# SCH_gps-tracker_2023-06-04.net
KiCad netlist of a schematic drawn in EasyEDA
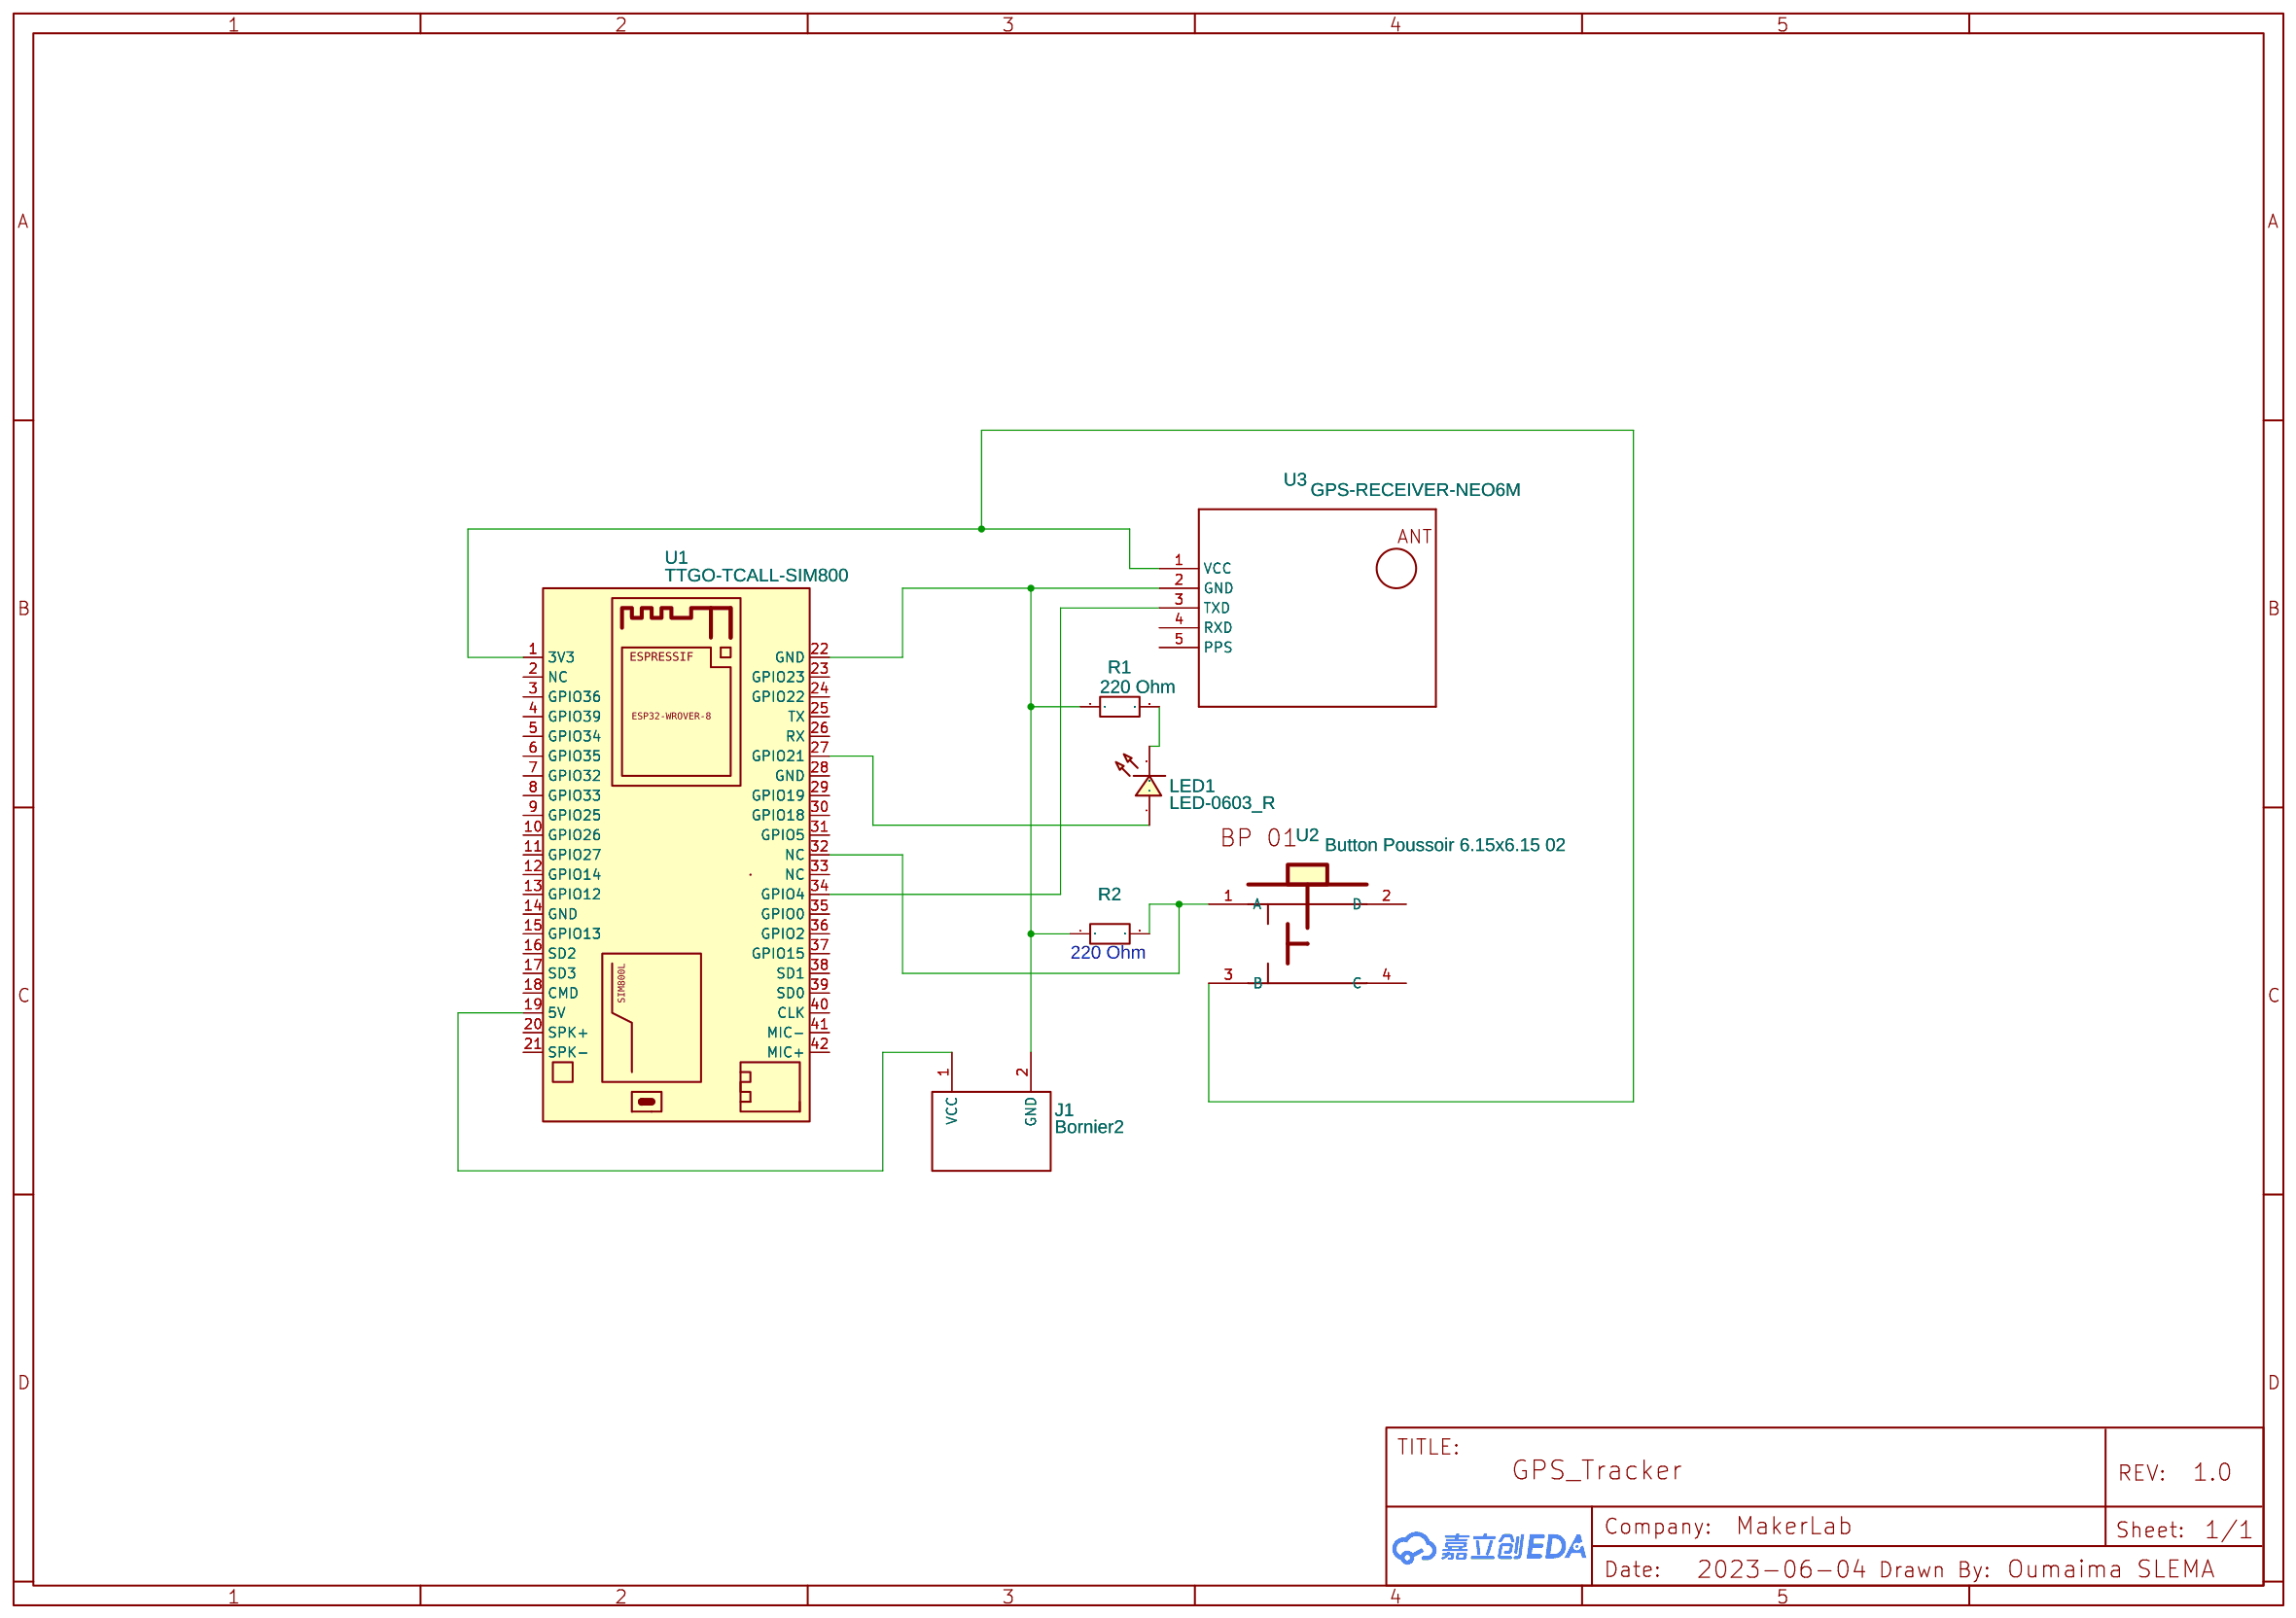
[diagram p0: schematic sheet]

(export (version "E")
  (design (tool "Eeschema 10.0.6"))
  (components
    (comp (ref "J1") (value "Bornier2") (libsource (lib "") (part "Bornier2")))
    (comp (ref "LED1")
      (value "LED-0603_R")
      (fields
        (field (name "BOM_Manufacturer Part") "19-217/R6C-AL1M2VY/3T")
        (field (name "BOM_Supplier Part") "C72044")
      )
      (libsource (lib "") (part "LED-0603_R"))
    )
    (comp (ref "R1") (value "220 Ohm") (libsource (lib "") (part "R_0603_EU")))
    (comp (ref "R2") (value "1k") (libsource (lib "") (part "R_0603_EU")))
    (comp (ref "U1") (value "TTGO-TCALL-SIM800") (libsource (lib "") (part "TTGO-TCALL-SIM800")))
    (comp (ref "U2")
      (value "Button Poussoir 6.15x6.15 02")
      (libsource (lib "") (part "Button Poussoir 6.15x6.15 02"))
    )
    (comp (ref "U3") (value "GPS-RECEIVER-NEO6M") (libsource (lib "") (part "GPS-RECEIVER-NEO6M")))
  )
  (nets
    (net (code "1") (name "Net-(J1-GND)") (class "Default")
      (node (ref "J1") (pin "2") (pinfunction "GND_2") (pintype "unspecified"))
      (node (ref "R1") (pin "1") (pinfunction "1_1") (pintype "unspecified"))
      (node (ref "R2") (pin "1") (pinfunction "1_1") (pintype "unspecified"))
      (node (ref "U1") (pin "22") (pinfunction "GND_22") (pintype "bidirectional"))
      (node (ref "U3") (pin "2") (pinfunction "GND_2") (pintype "unspecified"))
    )
    (net (code "2") (name "Net-(J1-VCC)") (class "Default")
      (node (ref "J1") (pin "1") (pinfunction "VCC_1") (pintype "unspecified"))
      (node (ref "U1") (pin "19") (pinfunction "5V_19") (pintype "bidirectional"))
    )
    (net (code "3") (name "Net-(LED1-Pad2)") (class "Default")
      (node (ref "LED1") (pin "2") (pinfunction "2_2") (pintype "unspecified"))
      (node (ref "R1") (pin "2") (pinfunction "2_2") (pintype "unspecified"))
    )
    (net (code "4") (name "Net-(U1-3V3)") (class "Default")
      (node (ref "U1") (pin "1") (pinfunction "3V3_1") (pintype "bidirectional"))
      (node (ref "U2") (pin "3") (pinfunction "B_3") (pintype "unspecified"))
      (node (ref "U3") (pin "1") (pinfunction "VCC_1") (pintype "unspecified"))
    )
    (net (code "5") (name "Net-(U1-GPIO4)") (class "Default")
      (node (ref "U1") (pin "34") (pinfunction "GPIO4_34") (pintype "unspecified"))
      (node (ref "U3") (pin "3") (pinfunction "TXD_3") (pintype "unspecified"))
    )
    (net (code "6") (name "Net-(U1-GPIO21)") (class "Default")
      (node (ref "LED1") (pin "1") (pinfunction "1_1") (pintype "unspecified"))
      (node (ref "U1") (pin "27") (pinfunction "GPIO21_27") (pintype "unspecified"))
    )
    (net (code "7") (name "Net-(U2-A)") (class "Default")
      (node (ref "R2") (pin "2") (pinfunction "2_2") (pintype "unspecified"))
      (node (ref "U1") (pin "32") (pinfunction "NC_32") (pintype "bidirectional"))
      (node (ref "U2") (pin "1") (pinfunction "A_1") (pintype "unspecified"))
    )
    (net (code "8") (name "unconnected-(U1-CLK-Pad40)") (class "Default")
      (node (ref "U1") (pin "40") (pinfunction "CLK_40") (pintype "unspecified"))
    )
    (net (code "9") (name "unconnected-(U1-CMD-Pad18)") (class "Default")
      (node (ref "U1") (pin "18") (pinfunction "CMD_18") (pintype "unspecified"))
    )
    (net (code "10") (name "unconnected-(U1-GND-Pad14)") (class "Default")
      (node (ref "U1") (pin "14") (pinfunction "GND_14") (pintype "bidirectional"))
    )
    (net (code "11") (name "unconnected-(U1-GND-Pad28)") (class "Default")
      (node (ref "U1") (pin "28") (pinfunction "GND_28") (pintype "bidirectional"))
    )
    (net (code "12") (name "unconnected-(U1-GPIO0-Pad35)") (class "Default")
      (node (ref "U1") (pin "35") (pinfunction "GPIO0_35") (pintype "unspecified"))
    )
    (net (code "13") (name "unconnected-(U1-GPIO2-Pad36)") (class "Default")
      (node (ref "U1") (pin "36") (pinfunction "GPIO2_36") (pintype "unspecified"))
    )
    (net (code "14") (name "unconnected-(U1-GPIO5-Pad31)") (class "Default")
      (node (ref "U1") (pin "31") (pinfunction "GPIO5_31") (pintype "unspecified"))
    )
    (net (code "15") (name "unconnected-(U1-GPIO12-Pad13)") (class "Default")
      (node (ref "U1") (pin "13") (pinfunction "GPIO12_13") (pintype "unspecified"))
    )
    (net (code "16") (name "unconnected-(U1-GPIO13-Pad15)") (class "Default")
      (node (ref "U1") (pin "15") (pinfunction "GPIO13_15") (pintype "unspecified"))
    )
    (net (code "17") (name "unconnected-(U1-GPIO14-Pad12)") (class "Default")
      (node (ref "U1") (pin "12") (pinfunction "GPIO14_12") (pintype "unspecified"))
    )
    (net (code "18") (name "unconnected-(U1-GPIO15-Pad37)") (class "Default")
      (node (ref "U1") (pin "37") (pinfunction "GPIO15_37") (pintype "unspecified"))
    )
    (net (code "19") (name "unconnected-(U1-GPIO18-Pad30)") (class "Default")
      (node (ref "U1") (pin "30") (pinfunction "GPIO18_30") (pintype "unspecified"))
    )
    (net (code "20") (name "unconnected-(U1-GPIO19-Pad29)") (class "Default")
      (node (ref "U1") (pin "29") (pinfunction "GPIO19_29") (pintype "unspecified"))
    )
    (net (code "21") (name "unconnected-(U1-GPIO22-Pad24)") (class "Default")
      (node (ref "U1") (pin "24") (pinfunction "GPIO22_24") (pintype "unspecified"))
    )
    (net (code "22") (name "unconnected-(U1-GPIO23-Pad23)") (class "Default")
      (node (ref "U1") (pin "23") (pinfunction "GPIO23_23") (pintype "unspecified"))
    )
    (net (code "23") (name "unconnected-(U1-GPIO25-Pad9)") (class "Default")
      (node (ref "U1") (pin "9") (pinfunction "GPIO25_9") (pintype "unspecified"))
    )
    (net (code "24") (name "unconnected-(U1-GPIO26-Pad10)") (class "Default")
      (node (ref "U1") (pin "10") (pinfunction "GPIO26_10") (pintype "unspecified"))
    )
    (net (code "25") (name "unconnected-(U1-GPIO27-Pad11)") (class "Default")
      (node (ref "U1") (pin "11") (pinfunction "GPIO27_11") (pintype "unspecified"))
    )
    (net (code "26") (name "unconnected-(U1-GPIO32-Pad7)") (class "Default")
      (node (ref "U1") (pin "7") (pinfunction "GPIO32_7") (pintype "unspecified"))
    )
    (net (code "27") (name "unconnected-(U1-GPIO33-Pad8)") (class "Default")
      (node (ref "U1") (pin "8") (pinfunction "GPIO33_8") (pintype "unspecified"))
    )
    (net (code "28") (name "unconnected-(U1-GPIO34-Pad5)") (class "Default")
      (node (ref "U1") (pin "5") (pinfunction "GPIO34_5") (pintype "unspecified"))
    )
    (net (code "29") (name "unconnected-(U1-GPIO35-Pad6)") (class "Default")
      (node (ref "U1") (pin "6") (pinfunction "GPIO35_6") (pintype "unspecified"))
    )
    (net (code "30") (name "unconnected-(U1-GPIO36-Pad3)") (class "Default")
      (node (ref "U1") (pin "3") (pinfunction "GPIO36_3") (pintype "unspecified"))
    )
    (net (code "31") (name "unconnected-(U1-GPIO39-Pad4)") (class "Default")
      (node (ref "U1") (pin "4") (pinfunction "GPIO39_4") (pintype "unspecified"))
    )
    (net (code "32") (name "unconnected-(U1-MIC+-Pad42)") (class "Default")
      (node (ref "U1") (pin "42") (pinfunction "MIC+_42") (pintype "bidirectional"))
    )
    (net (code "33") (name "unconnected-(U1-MIC--Pad41)") (class "Default")
      (node (ref "U1") (pin "41") (pinfunction "MIC-_41") (pintype "unspecified"))
    )
    (net (code "34") (name "unconnected-(U1-NC-Pad2)") (class "Default")
      (node (ref "U1") (pin "2") (pinfunction "NC_2") (pintype "bidirectional"))
    )
    (net (code "35") (name "unconnected-(U1-NC-Pad33)") (class "Default")
      (node (ref "U1") (pin "33") (pinfunction "NC_33") (pintype "bidirectional"))
    )
    (net (code "36") (name "unconnected-(U1-RX-Pad26)") (class "Default")
      (node (ref "U1") (pin "26") (pinfunction "RX_26") (pintype "unspecified"))
    )
    (net (code "37") (name "unconnected-(U1-SD0-Pad39)") (class "Default")
      (node (ref "U1") (pin "39") (pinfunction "SD0_39") (pintype "unspecified"))
    )
    (net (code "38") (name "unconnected-(U1-SD1-Pad38)") (class "Default")
      (node (ref "U1") (pin "38") (pinfunction "SD1_38") (pintype "unspecified"))
    )
    (net (code "39") (name "unconnected-(U1-SD2-Pad16)") (class "Default")
      (node (ref "U1") (pin "16") (pinfunction "SD2_16") (pintype "unspecified"))
    )
    (net (code "40") (name "unconnected-(U1-SD3-Pad17)") (class "Default")
      (node (ref "U1") (pin "17") (pinfunction "SD3_17") (pintype "unspecified"))
    )
    (net (code "41") (name "unconnected-(U1-SPK+-Pad20)") (class "Default")
      (node (ref "U1") (pin "20") (pinfunction "SPK+_20") (pintype "unspecified"))
    )
    (net (code "42") (name "unconnected-(U1-SPK--Pad21)") (class "Default")
      (node (ref "U1") (pin "21") (pinfunction "SPK-_21") (pintype "unspecified"))
    )
    (net (code "43") (name "unconnected-(U1-TX-Pad25)") (class "Default")
      (node (ref "U1") (pin "25") (pinfunction "TX_25") (pintype "unspecified"))
    )
    (net (code "44") (name "unconnected-(U2-C-Pad4)") (class "Default")
      (node (ref "U2") (pin "4") (pinfunction "C_4") (pintype "unspecified"))
    )
    (net (code "45") (name "unconnected-(U2-D-Pad2)") (class "Default")
      (node (ref "U2") (pin "2") (pinfunction "D_2") (pintype "unspecified"))
    )
    (net (code "46") (name "unconnected-(U3-PPS-Pad5)") (class "Default")
      (node (ref "U3") (pin "5") (pinfunction "PPS_5") (pintype "passive"))
    )
    (net (code "47") (name "unconnected-(U3-RXD-Pad4)") (class "Default")
      (node (ref "U3") (pin "4") (pinfunction "RXD_4") (pintype "passive"))
    )
  )
)
